# SCH_DART-Flight-Computer-5_2024-08-18.net
KiCad netlist of a schematic drawn in EasyEDA
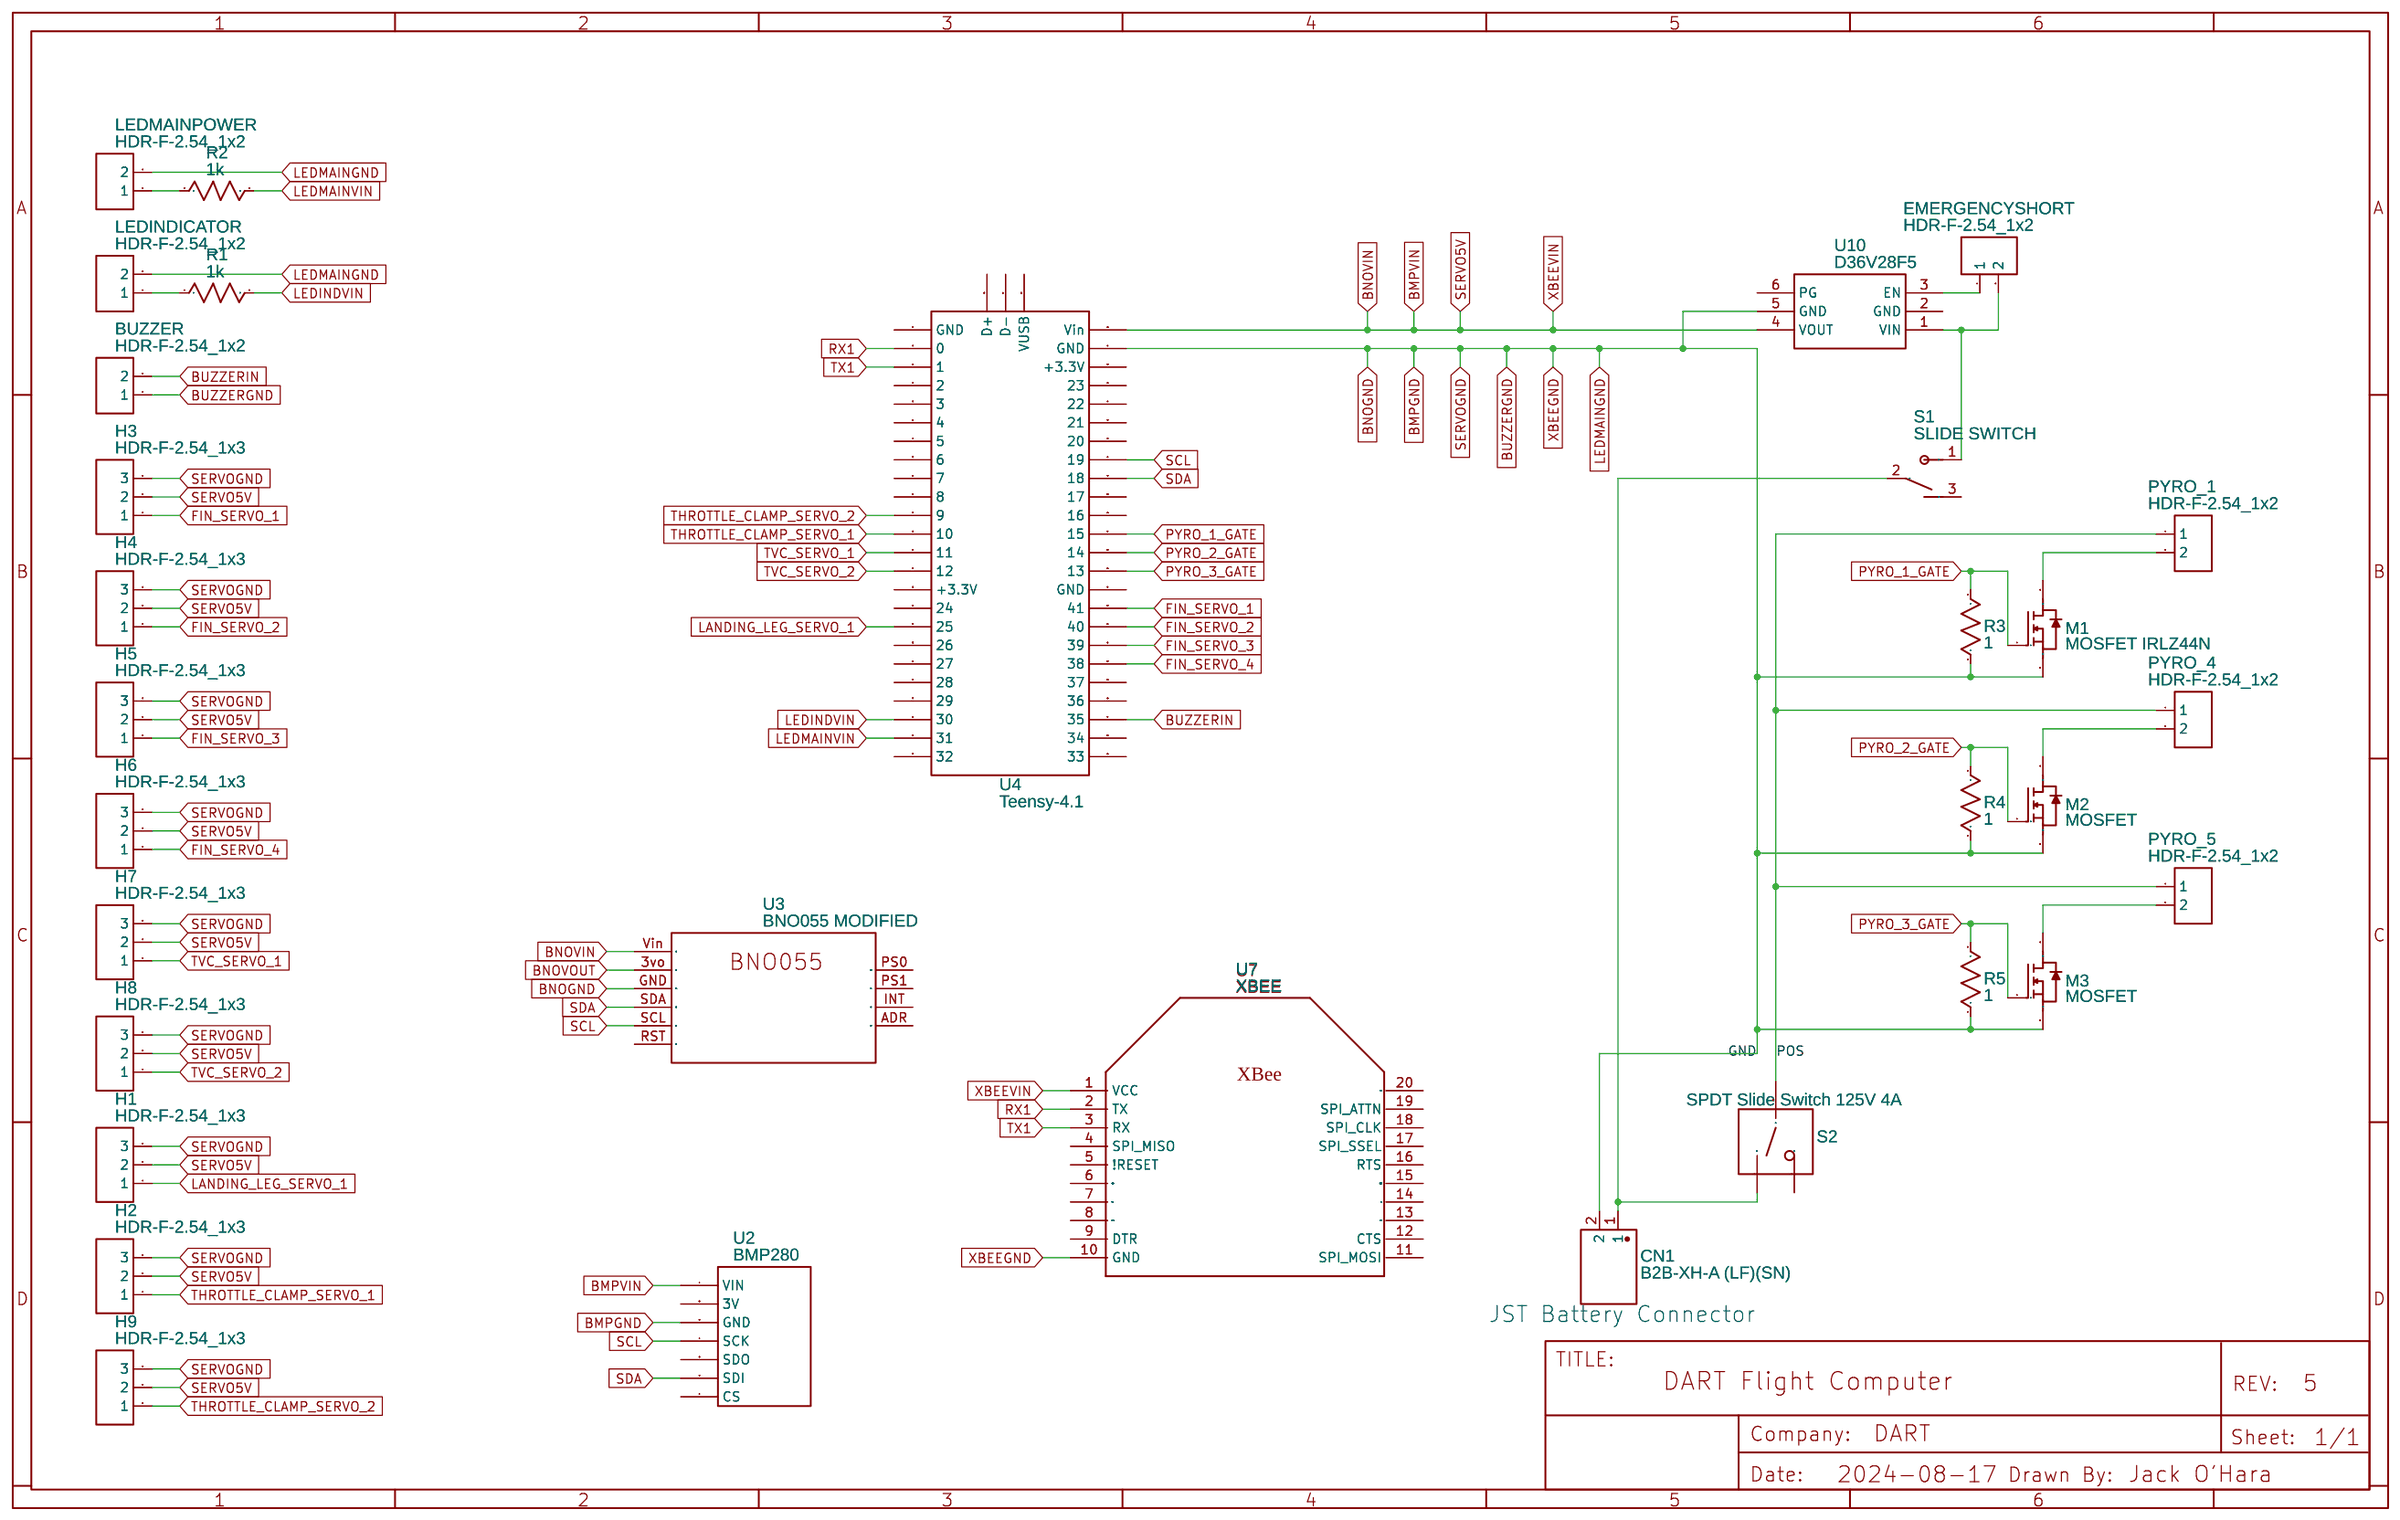
[diagram p0: schematic sheet]

(export (version "E")
  (design (tool "Eeschema 10.0.6"))
  (components
    (comp (ref "BUZZER") (value "HDR-F-2.54_1x2") (libsource (lib "") (part "HDR-F-2.54_1x2")))
    (comp (ref "CN1")
      (value "B2B-XH-A (LF)(SN)")
      (fields (field (name "Manufacturer Part") "B2B-XH-A(LF)(SN)") (field (name "Manufacturer") "JST"))
      (libsource (lib "") (part "B2B-XH-A (LF)(SN)"))
    )
    (comp (ref "EMERGENCYSHORT") (value "HDR-F-2.54_1x2") (libsource (lib "") (part "HDR-F-2.54_1x2_2")))
    (comp (ref "H1") (value "HDR-F-2.54_1x3") (libsource (lib "") (part "HDR-F-2.54_1x3")))
    (comp (ref "H2") (value "HDR-F-2.54_1x3") (libsource (lib "") (part "HDR-F-2.54_1x3")))
    (comp (ref "H3") (value "HDR-F-2.54_1x3") (libsource (lib "") (part "HDR-F-2.54_1x3")))
    (comp (ref "H4") (value "HDR-F-2.54_1x3") (libsource (lib "") (part "HDR-F-2.54_1x3")))
    (comp (ref "H5") (value "HDR-F-2.54_1x3") (libsource (lib "") (part "HDR-F-2.54_1x3")))
    (comp (ref "H6") (value "HDR-F-2.54_1x3") (libsource (lib "") (part "HDR-F-2.54_1x3")))
    (comp (ref "H7") (value "HDR-F-2.54_1x3") (libsource (lib "") (part "HDR-F-2.54_1x3")))
    (comp (ref "H8") (value "HDR-F-2.54_1x3") (libsource (lib "") (part "HDR-F-2.54_1x3")))
    (comp (ref "H9") (value "HDR-F-2.54_1x3") (libsource (lib "") (part "HDR-F-2.54_1x3")))
    (comp (ref "LEDINDICATOR") (value "HDR-F-2.54_1x2") (libsource (lib "") (part "HDR-F-2.54_1x2_1")))
    (comp (ref "LEDMAINPOWER") (value "HDR-F-2.54_1x2") (libsource (lib "") (part "HDR-F-2.54_1x2_4")))
    (comp (ref "M1") (value "MOSFET IRLZ44N") (libsource (lib "") (part "MOSFET")))
    (comp (ref "M2") (value "MOSFET") (libsource (lib "") (part "MOSFET")))
    (comp (ref "M3") (value "MOSFET") (libsource (lib "") (part "MOSFET")))
    (comp (ref "PYRO_1") (value "HDR-F-2.54_1x2") (libsource (lib "") (part "HDR-F-2.54_1x2_3")))
    (comp (ref "PYRO_4") (value "HDR-F-2.54_1x2") (libsource (lib "") (part "HDR-F-2.54_1x2_3")))
    (comp (ref "PYRO_5") (value "HDR-F-2.54_1x2") (libsource (lib "") (part "HDR-F-2.54_1x2_3")))
    (comp (ref "R1") (value "1k") (libsource (lib "") (part "R_0603_US_1")))
    (comp (ref "R2") (value "1k") (libsource (lib "") (part "R_0603_US_1")))
    (comp (ref "R3") (value "1") (libsource (lib "") (part "R_0603_US")))
    (comp (ref "R4") (value "1") (libsource (lib "") (part "R_0603_US")))
    (comp (ref "R5") (value "1") (libsource (lib "") (part "R_0603_US")))
    (comp (ref "S1") (value "SLIDE SWITCH") (libsource (lib "") (part "SLIDE SWITCH")))
    (comp (ref "S2")
      (value "SPDT Slide Switch 125V 4A")
      (fields
        (field (name "Manufacturer Part") "8SS1012-Z")
        (field (name "Manufacturer") "Nidec Copal Electronics")
      )
      (libsource (lib "") (part "SPDT Slide Switch 125V 4A"))
    )
    (comp (ref "U2") (value "BMP280") (libsource (lib "") (part "BMP280")))
    (comp (ref "U3") (value "BNO055 MODIFIED") (libsource (lib "") (part "BNO055 MODIFIED")))
    (comp (ref "U4") (value "Teensy-4.1") (libsource (lib "") (part "Teensy-4.1")))
    (comp (ref "U7") (value "XBEE") (libsource (lib "") (part "XBEE")))
    (comp (ref "U10")
      (value "D36V28F5")
      (fields
        (field (name "Manufacturer Part") "Pololu D36V28F5 Step-down regulator 5v fixed")
        (field (name "Manufacturer") "Pololu")
      )
      (libsource (lib "") (part "D36V28F5"))
    )
  )
  (nets
    (net (code "1") (name "/POS") (class "Default")
      (node (ref "PYRO_1") (pin "1") (pinfunction "1_1") (pintype "input"))
      (node (ref "PYRO_4") (pin "1") (pinfunction "1_1") (pintype "input"))
      (node (ref "PYRO_5") (pin "1") (pinfunction "1_1") (pintype "input"))
      (node (ref "S2") (pin "2") (pinfunction "2_2") (pintype "unspecified"))
    )
    (net (code "2") (name "BMPGND") (class "Default")
      (node (ref "BUZZER") (pin "1") (pinfunction "1_1") (pintype "input"))
      (node (ref "CN1") (pin "2") (pinfunction "2_2") (pintype "unspecified"))
      (node (ref "H1") (pin "3") (pinfunction "3_3") (pintype "input"))
      (node (ref "H2") (pin "3") (pinfunction "3_3") (pintype "input"))
      (node (ref "H3") (pin "3") (pinfunction "3_3") (pintype "input"))
      (node (ref "H4") (pin "3") (pinfunction "3_3") (pintype "input"))
      (node (ref "H5") (pin "3") (pinfunction "3_3") (pintype "input"))
      (node (ref "H6") (pin "3") (pinfunction "3_3") (pintype "input"))
      (node (ref "H7") (pin "3") (pinfunction "3_3") (pintype "input"))
      (node (ref "H8") (pin "3") (pinfunction "3_3") (pintype "input"))
      (node (ref "H9") (pin "3") (pinfunction "3_3") (pintype "input"))
      (node (ref "LEDINDICATOR") (pin "2") (pinfunction "2_2") (pintype "input"))
      (node (ref "LEDMAINPOWER") (pin "2") (pinfunction "2_2") (pintype "input"))
      (node (ref "M1") (pin "2") (pinfunction "2_2") (pintype "unspecified"))
      (node (ref "M2") (pin "2") (pinfunction "2_2") (pintype "unspecified"))
      (node (ref "M3") (pin "2") (pinfunction "2_2") (pintype "unspecified"))
      (node (ref "R3") (pin "1") (pinfunction "1_1") (pintype "unspecified"))
      (node (ref "R4") (pin "1") (pinfunction "1_1") (pintype "unspecified"))
      (node (ref "R5") (pin "1") (pinfunction "1_1") (pintype "unspecified"))
      (node (ref "U10") (pin "5") (pinfunction "GND_5") (pintype "unspecified"))
      (node (ref "U2") (pin "5") (pinfunction "GND_5") (pintype "unspecified"))
      (node (ref "U3") (pin "GND") (pinfunction "GND_GND") (pintype "unspecified"))
      (node (ref "U4") (pin "47") (pinfunction "GND_47") (pintype "unspecified"))
      (node (ref "U7") (pin "10") (pinfunction "GND_10") (pintype "unspecified"))
    )
    (net (code "3") (name "BMPVIN") (class "Default")
      (node (ref "H1") (pin "2") (pinfunction "2_2") (pintype "input"))
      (node (ref "H2") (pin "2") (pinfunction "2_2") (pintype "input"))
      (node (ref "H3") (pin "2") (pinfunction "2_2") (pintype "input"))
      (node (ref "H4") (pin "2") (pinfunction "2_2") (pintype "input"))
      (node (ref "H5") (pin "2") (pinfunction "2_2") (pintype "input"))
      (node (ref "H6") (pin "2") (pinfunction "2_2") (pintype "input"))
      (node (ref "H7") (pin "2") (pinfunction "2_2") (pintype "input"))
      (node (ref "H8") (pin "2") (pinfunction "2_2") (pintype "input"))
      (node (ref "H9") (pin "2") (pinfunction "2_2") (pintype "input"))
      (node (ref "U10") (pin "4") (pinfunction "VOUT_4") (pintype "unspecified"))
      (node (ref "U2") (pin "7") (pinfunction "VIN_7") (pintype "unspecified"))
      (node (ref "U3") (pin "Vin") (pinfunction "Vin_Vin") (pintype "unspecified"))
      (node (ref "U4") (pin "48") (pinfunction "Vin_48") (pintype "unspecified"))
      (node (ref "U7") (pin "1") (pinfunction "VCC_1") (pintype "unspecified"))
    )
    (net (code "4") (name "BNOVOUT") (class "Default")
      (node (ref "U3") (pin "3vo") (pinfunction "3vo_3vo") (pintype "unspecified"))
    )
    (net (code "5") (name "BUZZERIN") (class "Default")
      (node (ref "BUZZER") (pin "2") (pinfunction "2_2") (pintype "input"))
      (node (ref "U4") (pin "27") (pinfunction "35_27") (pintype "unspecified"))
    )
    (net (code "6") (name "FIN_SERVO_1") (class "Default")
      (node (ref "H3") (pin "1") (pinfunction "1_1") (pintype "input"))
      (node (ref "U4") (pin "33") (pinfunction "41_33") (pintype "unspecified"))
    )
    (net (code "7") (name "FIN_SERVO_2") (class "Default")
      (node (ref "H4") (pin "1") (pinfunction "1_1") (pintype "input"))
      (node (ref "U4") (pin "32") (pinfunction "40_32") (pintype "unspecified"))
    )
    (net (code "8") (name "FIN_SERVO_3") (class "Default")
      (node (ref "H5") (pin "1") (pinfunction "1_1") (pintype "input"))
      (node (ref "U4") (pin "31") (pinfunction "39_31") (pintype "unspecified"))
    )
    (net (code "9") (name "FIN_SERVO_4") (class "Default")
      (node (ref "H6") (pin "1") (pinfunction "1_1") (pintype "input"))
      (node (ref "U4") (pin "30") (pinfunction "38_30") (pintype "unspecified"))
    )
    (net (code "10") (name "LANDING_LEG_SERVO_1") (class "Default")
      (node (ref "H1") (pin "1") (pinfunction "1_1") (pintype "input"))
      (node (ref "U4") (pin "17") (pinfunction "25_17") (pintype "unspecified"))
    )
    (net (code "11") (name "LEDINDVIN") (class "Default")
      (node (ref "R1") (pin "2") (pinfunction "2_2") (pintype "unspecified"))
      (node (ref "U4") (pin "22") (pinfunction "30_22") (pintype "unspecified"))
    )
    (net (code "12") (name "LEDMAINVIN") (class "Default")
      (node (ref "R2") (pin "2") (pinfunction "2_2") (pintype "unspecified"))
      (node (ref "U4") (pin "23") (pinfunction "31_23") (pintype "unspecified"))
    )
    (net (code "13") (name "Net-(CN1-Pad1)") (class "Default")
      (node (ref "CN1") (pin "1") (pinfunction "1_1") (pintype "unspecified"))
      (node (ref "S1") (pin "2") (pinfunction "2_2") (pintype "bidirectional"))
      (node (ref "S2") (pin "3") (pinfunction "3_3") (pintype "unspecified"))
    )
    (net (code "14") (name "Net-(LEDINDICATOR-Pad1)") (class "Default")
      (node (ref "LEDINDICATOR") (pin "1") (pinfunction "1_1") (pintype "input"))
      (node (ref "R1") (pin "1") (pinfunction "1_1") (pintype "unspecified"))
    )
    (net (code "15") (name "Net-(LEDMAINPOWER-Pad1)") (class "Default")
      (node (ref "LEDMAINPOWER") (pin "1") (pinfunction "1_1") (pintype "input"))
      (node (ref "R2") (pin "1") (pinfunction "1_1") (pintype "unspecified"))
    )
    (net (code "16") (name "Net-(M1-Pad3)") (class "Default")
      (node (ref "M1") (pin "3") (pinfunction "3_3") (pintype "unspecified"))
      (node (ref "PYRO_1") (pin "2") (pinfunction "2_2") (pintype "input"))
    )
    (net (code "17") (name "Net-(M2-Pad3)") (class "Default")
      (node (ref "M2") (pin "3") (pinfunction "3_3") (pintype "unspecified"))
      (node (ref "PYRO_4") (pin "2") (pinfunction "2_2") (pintype "input"))
    )
    (net (code "18") (name "Net-(M3-Pad3)") (class "Default")
      (node (ref "M3") (pin "3") (pinfunction "3_3") (pintype "unspecified"))
      (node (ref "PYRO_5") (pin "2") (pinfunction "2_2") (pintype "input"))
    )
    (net (code "19") (name "Net-(U10-EN)") (class "Default")
      (node (ref "EMERGENCYSHORT") (pin "1") (pinfunction "1_1") (pintype "input"))
      (node (ref "U10") (pin "3") (pinfunction "EN_3") (pintype "unspecified"))
    )
    (net (code "20") (name "Net-(U10-VIN)") (class "Default")
      (node (ref "EMERGENCYSHORT") (pin "2") (pinfunction "2_2") (pintype "input"))
      (node (ref "S1") (pin "1") (pinfunction "1_1") (pintype "bidirectional"))
      (node (ref "U10") (pin "1") (pinfunction "VIN_1") (pintype "unspecified"))
    )
    (net (code "21") (name "PYRO_1_GATE") (class "Default")
      (node (ref "M1") (pin "1") (pinfunction "1_1") (pintype "unspecified"))
      (node (ref "R3") (pin "2") (pinfunction "2_2") (pintype "unspecified"))
      (node (ref "U4") (pin "37") (pinfunction "15_37") (pintype "unspecified"))
    )
    (net (code "22") (name "PYRO_2_GATE") (class "Default")
      (node (ref "M2") (pin "1") (pinfunction "1_1") (pintype "unspecified"))
      (node (ref "R4") (pin "2") (pinfunction "2_2") (pintype "unspecified"))
      (node (ref "U4") (pin "36") (pinfunction "14_36") (pintype "unspecified"))
    )
    (net (code "23") (name "PYRO_3_GATE") (class "Default")
      (node (ref "M3") (pin "1") (pinfunction "1_1") (pintype "unspecified"))
      (node (ref "R5") (pin "2") (pinfunction "2_2") (pintype "unspecified"))
      (node (ref "U4") (pin "35") (pinfunction "13_35") (pintype "unspecified"))
    )
    (net (code "24") (name "RX1") (class "Default")
      (node (ref "U4") (pin "2") (pinfunction "0_2") (pintype "unspecified"))
      (node (ref "U7") (pin "2") (pinfunction "TX_2") (pintype "output"))
    )
    (net (code "25") (name "SCL") (class "Default")
      (node (ref "U2") (pin "4") (pinfunction "SCK_4") (pintype "unspecified"))
      (node (ref "U3") (pin "SCL") (pinfunction "SCL_SCL") (pintype "unspecified"))
      (node (ref "U4") (pin "41") (pinfunction "19_41") (pintype "unspecified"))
    )
    (net (code "26") (name "SDA") (class "Default")
      (node (ref "U2") (pin "2") (pinfunction "SDI_2") (pintype "unspecified"))
      (node (ref "U3") (pin "SDA") (pinfunction "SDA_SDA") (pintype "unspecified"))
      (node (ref "U4") (pin "40") (pinfunction "18_40") (pintype "unspecified"))
    )
    (net (code "27") (name "THROTTLE_CLAMP_SERVO_1") (class "Default")
      (node (ref "H2") (pin "1") (pinfunction "1_1") (pintype "input"))
      (node (ref "U4") (pin "12") (pinfunction "10_12") (pintype "unspecified"))
    )
    (net (code "28") (name "THROTTLE_CLAMP_SERVO_2") (class "Default")
      (node (ref "H9") (pin "1") (pinfunction "1_1") (pintype "input"))
      (node (ref "U4") (pin "11") (pinfunction "9_11") (pintype "unspecified"))
    )
    (net (code "29") (name "TVC_SERVO_1") (class "Default")
      (node (ref "H7") (pin "1") (pinfunction "1_1") (pintype "input"))
      (node (ref "U4") (pin "13") (pinfunction "11_13") (pintype "unspecified"))
    )
    (net (code "30") (name "TVC_SERVO_2") (class "Default")
      (node (ref "H8") (pin "1") (pinfunction "1_1") (pintype "input"))
      (node (ref "U4") (pin "14") (pinfunction "12_14") (pintype "unspecified"))
    )
    (net (code "31") (name "TX1") (class "Default")
      (node (ref "U4") (pin "3") (pinfunction "1_3") (pintype "unspecified"))
      (node (ref "U7") (pin "3") (pinfunction "RX_3") (pintype "input"))
    )
    (net (code "32") (name "unconnected-(S1-Pad3)") (class "Default")
      (node (ref "S1") (pin "3") (pinfunction "3_3") (pintype "bidirectional"))
    )
    (net (code "33") (name "unconnected-(S2-Pad1)") (class "Default")
      (node (ref "S2") (pin "1") (pinfunction "1_1") (pintype "unspecified"))
    )
    (net (code "34") (name "unconnected-(U2-3V-Pad6)") (class "Default")
      (node (ref "U2") (pin "6") (pinfunction "3V_6") (pintype "unspecified"))
    )
    (net (code "35") (name "unconnected-(U2-CS-Pad1)") (class "Default")
      (node (ref "U2") (pin "1") (pinfunction "CS_1") (pintype "unspecified"))
    )
    (net (code "36") (name "unconnected-(U2-SDO-Pad3)") (class "Default")
      (node (ref "U2") (pin "3") (pinfunction "SDO_3") (pintype "unspecified"))
    )
    (net (code "37") (name "unconnected-(U3-PadADR)") (class "Default")
      (node (ref "U3") (pin "ADR") (pinfunction "ADR_ADR") (pintype "unspecified"))
    )
    (net (code "38") (name "unconnected-(U3-PadINT)") (class "Default")
      (node (ref "U3") (pin "INT") (pinfunction "INT_INT") (pintype "unspecified"))
    )
    (net (code "39") (name "unconnected-(U3-PadPS0)") (class "Default")
      (node (ref "U3") (pin "PS0") (pinfunction "PS0_PS0") (pintype "unspecified"))
    )
    (net (code "40") (name "unconnected-(U3-PadPS1)") (class "Default")
      (node (ref "U3") (pin "PS1") (pinfunction "PS1_PS1") (pintype "unspecified"))
    )
    (net (code "41") (name "unconnected-(U3-PadRST)") (class "Default")
      (node (ref "U3") (pin "RST") (pinfunction "RST_RST") (pintype "unspecified"))
    )
    (net (code "42") (name "unconnected-(U4-+3.3V-Pad15)") (class "Default")
      (node (ref "U4") (pin "15") (pinfunction "+3.3V_15") (pintype "unspecified"))
    )
    (net (code "43") (name "unconnected-(U4-+3.3V-Pad46)") (class "Default")
      (node (ref "U4") (pin "46") (pinfunction "+3.3V_46") (pintype "unspecified"))
    )
    (net (code "44") (name "unconnected-(U4-2-Pad4)") (class "Default")
      (node (ref "U4") (pin "4") (pinfunction "2_4") (pintype "unspecified"))
    )
    (net (code "45") (name "unconnected-(U4-3-Pad5)") (class "Default")
      (node (ref "U4") (pin "5") (pinfunction "3_5") (pintype "unspecified"))
    )
    (net (code "46") (name "unconnected-(U4-4-Pad6)") (class "Default")
      (node (ref "U4") (pin "6") (pinfunction "4_6") (pintype "unspecified"))
    )
    (net (code "47") (name "unconnected-(U4-5-Pad7)") (class "Default")
      (node (ref "U4") (pin "7") (pinfunction "5_7") (pintype "unspecified"))
    )
    (net (code "48") (name "unconnected-(U4-6-Pad8)") (class "Default")
      (node (ref "U4") (pin "8") (pinfunction "6_8") (pintype "unspecified"))
    )
    (net (code "49") (name "unconnected-(U4-7-Pad9)") (class "Default")
      (node (ref "U4") (pin "9") (pinfunction "7_9") (pintype "unspecified"))
    )
    (net (code "50") (name "unconnected-(U4-8-Pad10)") (class "Default")
      (node (ref "U4") (pin "10") (pinfunction "8_10") (pintype "unspecified"))
    )
    (net (code "51") (name "unconnected-(U4-16-Pad38)") (class "Default")
      (node (ref "U4") (pin "38") (pinfunction "16_38") (pintype "unspecified"))
    )
    (net (code "52") (name "unconnected-(U4-17-Pad39)") (class "Default")
      (node (ref "U4") (pin "39") (pinfunction "17_39") (pintype "unspecified"))
    )
    (net (code "53") (name "unconnected-(U4-20-Pad42)") (class "Default")
      (node (ref "U4") (pin "42") (pinfunction "20_42") (pintype "unspecified"))
    )
    (net (code "54") (name "unconnected-(U4-21-Pad43)") (class "Default")
      (node (ref "U4") (pin "43") (pinfunction "21_43") (pintype "unspecified"))
    )
    (net (code "55") (name "unconnected-(U4-22-Pad44)") (class "Default")
      (node (ref "U4") (pin "44") (pinfunction "22_44") (pintype "unspecified"))
    )
    (net (code "56") (name "unconnected-(U4-23-Pad45)") (class "Default")
      (node (ref "U4") (pin "45") (pinfunction "23_45") (pintype "unspecified"))
    )
    (net (code "57") (name "unconnected-(U4-24-Pad16)") (class "Default")
      (node (ref "U4") (pin "16") (pinfunction "24_16") (pintype "unspecified"))
    )
    (net (code "58") (name "unconnected-(U4-26-Pad18)") (class "Default")
      (node (ref "U4") (pin "18") (pinfunction "26_18") (pintype "unspecified"))
    )
    (net (code "59") (name "unconnected-(U4-27-Pad19)") (class "Default")
      (node (ref "U4") (pin "19") (pinfunction "27_19") (pintype "unspecified"))
    )
    (net (code "60") (name "unconnected-(U4-28-Pad20)") (class "Default")
      (node (ref "U4") (pin "20") (pinfunction "28_20") (pintype "unspecified"))
    )
    (net (code "61") (name "unconnected-(U4-29-Pad21)") (class "Default")
      (node (ref "U4") (pin "21") (pinfunction "29_21") (pintype "unspecified"))
    )
    (net (code "62") (name "unconnected-(U4-32-Pad24)") (class "Default")
      (node (ref "U4") (pin "24") (pinfunction "32_24") (pintype "unspecified"))
    )
    (net (code "63") (name "unconnected-(U4-33-Pad25)") (class "Default")
      (node (ref "U4") (pin "25") (pinfunction "33_25") (pintype "unspecified"))
    )
    (net (code "64") (name "unconnected-(U4-34-Pad26)") (class "Default")
      (node (ref "U4") (pin "26") (pinfunction "34_26") (pintype "unspecified"))
    )
    (net (code "65") (name "unconnected-(U4-36-Pad28)") (class "Default")
      (node (ref "U4") (pin "28") (pinfunction "36_28") (pintype "unspecified"))
    )
    (net (code "66") (name "unconnected-(U4-37-Pad29)") (class "Default")
      (node (ref "U4") (pin "29") (pinfunction "37_29") (pintype "unspecified"))
    )
    (net (code "67") (name "unconnected-(U4-D+-Pad66)") (class "Default")
      (node (ref "U4") (pin "66") (pinfunction "D+_66") (pintype "unspecified"))
    )
    (net (code "68") (name "unconnected-(U4-D--Pad67)") (class "Default")
      (node (ref "U4") (pin "67") (pinfunction "D-_67") (pintype "unspecified"))
    )
    (net (code "69") (name "unconnected-(U4-GND-Pad1)") (class "Default")
      (node (ref "U4") (pin "1") (pinfunction "GND_1") (pintype "unspecified"))
    )
    (net (code "70") (name "unconnected-(U4-GND-Pad34)") (class "Default")
      (node (ref "U4") (pin "34") (pinfunction "GND_34") (pintype "unspecified"))
    )
    (net (code "71") (name "unconnected-(U4-VUSB-Pad52)") (class "Default")
      (node (ref "U4") (pin "52") (pinfunction "VUSB_52") (pintype "unspecified"))
    )
    (net (code "72") (name "unconnected-(U7-!RESET-Pad5)") (class "Default")
      (node (ref "U7") (pin "5") (pinfunction "!RESET_5") (pintype "input"))
    )
    (net (code "73") (name "unconnected-(U7-AD0DIO0-Pad20)") (class "Default")
      (node (ref "U7") (pin "20") (pinfunction "AD0DIO0_20") (pintype "unspecified"))
    )
    (net (code "74") (name "unconnected-(U7-ASCAD5DIO5-Pad15)") (class "Default")
      (node (ref "U7") (pin "15") (pinfunction "ASCAD5DIO5_15") (pintype "unspecified"))
    )
    (net (code "75") (name "unconnected-(U7-CTS-Pad12)") (class "Default")
      (node (ref "U7") (pin "12") (pinfunction "CTS_12") (pintype "unspecified"))
    )
    (net (code "76") (name "unconnected-(U7-DTR-Pad9)") (class "Default")
      (node (ref "U7") (pin "9") (pinfunction "DTR_9") (pintype "unspecified"))
    )
    (net (code "77") (name "unconnected-(U7-ONSLEEP-Pad13)") (class "Default")
      (node (ref "U7") (pin "13") (pinfunction "ONSLEEP_13") (pintype "output"))
    )
    (net (code "78") (name "unconnected-(U7-PWM0RSSI-Pad6)") (class "Default")
      (node (ref "U7") (pin "6") (pinfunction "PWM0RSSI_6") (pintype "output"))
    )
    (net (code "79") (name "unconnected-(U7-PWM1-Pad7)") (class "Default")
      (node (ref "U7") (pin "7") (pinfunction "PWM1_7") (pintype "output"))
    )
    (net (code "80") (name "unconnected-(U7-RESERVED-Pad8)") (class "Default")
      (node (ref "U7") (pin "8") (pinfunction "RESERVED_8") (pintype "unspecified"))
    )
    (net (code "81") (name "unconnected-(U7-RTS-Pad16)") (class "Default")
      (node (ref "U7") (pin "16") (pinfunction "RTS_16") (pintype "unspecified"))
    )
    (net (code "82") (name "unconnected-(U7-SPI_ATTN-Pad19)") (class "Default")
      (node (ref "U7") (pin "19") (pinfunction "SPI_ATTN_19") (pintype "unspecified"))
    )
    (net (code "83") (name "unconnected-(U7-SPI_CLK-Pad18)") (class "Default")
      (node (ref "U7") (pin "18") (pinfunction "SPI_CLK_18") (pintype "unspecified"))
    )
    (net (code "84") (name "unconnected-(U7-SPI_MISO-Pad4)") (class "Default")
      (node (ref "U7") (pin "4") (pinfunction "SPI_MISO_4") (pintype "output"))
    )
    (net (code "85") (name "unconnected-(U7-SPI_MOSI-Pad11)") (class "Default")
      (node (ref "U7") (pin "11") (pinfunction "SPI_MOSI_11") (pintype "unspecified"))
    )
    (net (code "86") (name "unconnected-(U7-SPI_SSEL-Pad17)") (class "Default")
      (node (ref "U7") (pin "17") (pinfunction "SPI_SSEL_17") (pintype "unspecified"))
    )
    (net (code "87") (name "unconnected-(U7-VREF-Pad14)") (class "Default")
      (node (ref "U7") (pin "14") (pinfunction "VREF_14") (pintype "input"))
    )
    (net (code "88") (name "unconnected-(U10-GND-Pad2)") (class "Default")
      (node (ref "U10") (pin "2") (pinfunction "GND_2") (pintype "unspecified"))
    )
    (net (code "89") (name "unconnected-(U10-PG-Pad6)") (class "Default")
      (node (ref "U10") (pin "6") (pinfunction "PG_6") (pintype "unspecified"))
    )
  )
)
